# 100_UART_FLASH.net
KiCad netlist of a schematic drawn in Altium Designer
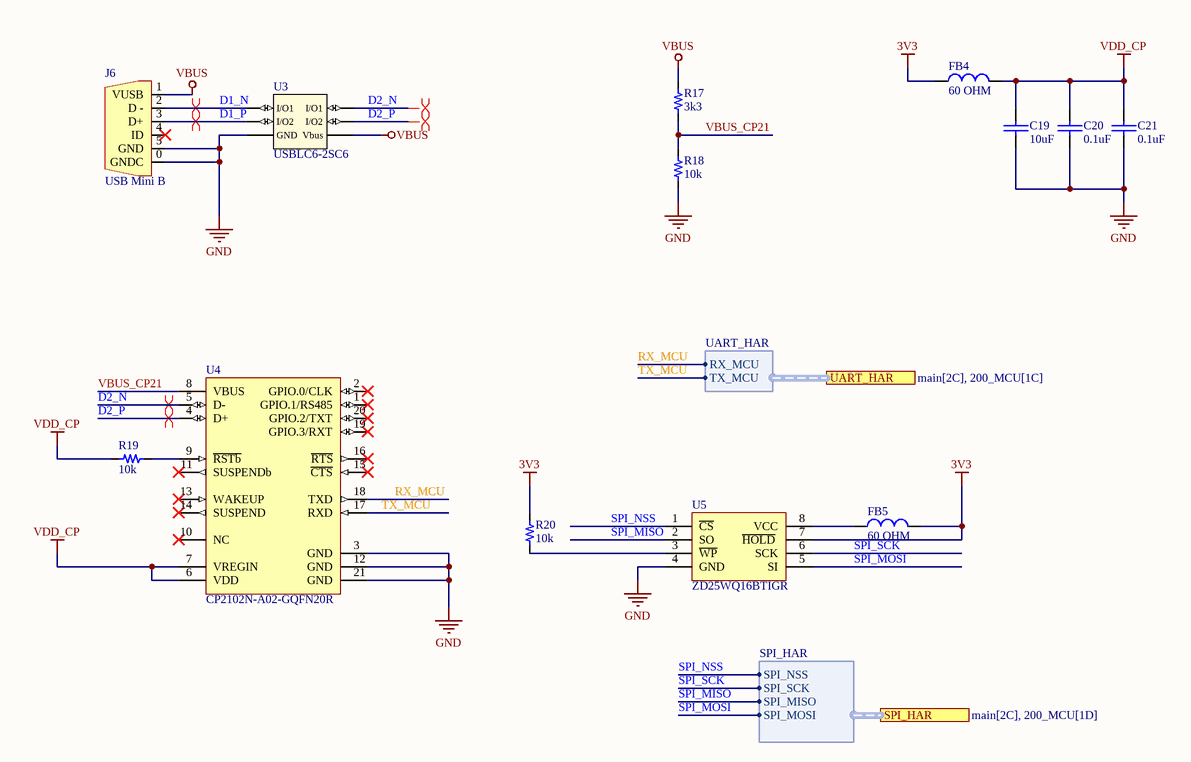
[diagram p0: 100_UART_FLASH.SchDoc]

(export (version "E")
  (design (tool "Eeschema 10.0.6"))
  (components
    (comp (ref "C19")
      (value "10uF")
      (footprint "0603_cap")
      (description "10V 10uF X5R ±10% 0603 Multilayer Ceramic Capacitors MLCC - SMD/SMT ROHS")
      (fields
        (field (name "MANUFACTURER") "CCTC")
        (field (name "MANUFACTURER PART NUMBER") "TCC0603X5R106K100CT")
      )
      (libsource (lib "shared_lib") (part "Cap_10uF_0603_10V"))
    )
    (comp (ref "C20")
      (value "0.1uF")
      (footprint "0603_cap")
      (description "50V 100nF Y5V -20%~+80% 0603 Multilayer Ceramic Capacitors MLCC - SMD/SMT ROHS")
      (fields
        (field (name "MANUFACTURER") "Walsin Tech Corp")
        (field (name "MANUFACTURER PART NUMBER") "0603F104Z500CT")
      )
      (libsource (lib "shared_lib") (part "Cap_0.1uF_0603_50V"))
    )
    (comp (ref "C21")
      (value "0.1uF")
      (footprint "0603_cap")
      (description "50V 100nF Y5V -20%~+80% 0603 Multilayer Ceramic Capacitors MLCC - SMD/SMT ROHS")
      (fields
        (field (name "MANUFACTURER") "Walsin Tech Corp")
        (field (name "MANUFACTURER PART NUMBER") "0603F104Z500CT")
      )
      (libsource (lib "shared_lib") (part "Cap_0.1uF_0603_50V"))
    )
    (comp (ref "FB4")
      (value "60 OHM")
      (footprint "0603_fb")
      (description "2A 1 100mΩ 60Ω@100MHz ±25% 0603 Ferrite Beads ROHS")
      (fields
        (field (name "MANUFACTURER") "TAI-TECH")
        (field (name "MANUFACTURER PART NUMBER") "HCB1608KF-600T20")
      )
      (libsource (lib "shared_lib") (part "FB_60_0603_2A"))
    )
    (comp (ref "FB5")
      (value "60 OHM")
      (footprint "0603_fb")
      (description "2A 1 100mΩ 60Ω@100MHz ±25% 0603 Ferrite Beads ROHS")
      (fields
        (field (name "MANUFACTURER") "TAI-TECH")
        (field (name "MANUFACTURER PART NUMBER") "HCB1608KF-600T20")
      )
      (libsource (lib "shared_lib") (part "FB_60_0603_2A"))
    )
    (comp (ref "J6")
      (value "USB Mini B")
      (footprint "CON_5x1_SMD_miniUSB_B")
      (description "CONN RCPT USB2.0 MINI B SMD R/A")
      (fields
        (field (name "MANUFACTURER PART NUMBER") "KH-MINI-SMT-5P-Cu")
        (field (name "MANUFACTURER") "EDAC Inc.")
      )
      (libsource (lib "shared_lib") (part "Con_Mini_USB_B"))
    )
    (comp (ref "R17")
      (value "3k3")
      (footprint "0603_res")
      (description "RES SMD 3k3 OHM 5% 1/10W 0603")
      (fields
        (field (name "MANUFACTURER") "FOJAN")
        (field (name "MANUFACTURER PART NUMBER") "FRC0603J332 TS")
      )
      (libsource (lib "shared_lib") (part "Res_3k3_0603_1/10W"))
    )
    (comp (ref "R18")
      (value "10k")
      (footprint "0603_res")
      (description "RES SMD 10k OHM 5% 1/10W 0603")
      (fields (field (name "MANUFACTURER") "FOJAN") (field (name "MANUFACTURER PART NUMBER") "FRC0603J103TS"))
      (libsource (lib "shared_lib") (part "Res_10k_0603_1/10W"))
    )
    (comp (ref "R19")
      (value "10k")
      (footprint "0603_res")
      (description "RES SMD 10k OHM 5% 1/10W 0603")
      (fields (field (name "MANUFACTURER") "FOJAN") (field (name "MANUFACTURER PART NUMBER") "FRC0603J103TS"))
      (libsource (lib "shared_lib") (part "Res_10k_0603_1/10W"))
    )
    (comp (ref "R20")
      (value "10k")
      (footprint "0603_res")
      (description "RES SMD 10k OHM 5% 1/10W 0603")
      (fields (field (name "MANUFACTURER") "FOJAN") (field (name "MANUFACTURER PART NUMBER") "FRC0603J103TS"))
      (libsource (lib "shared_lib") (part "Res_10k_0603_1/10W"))
    )
    (comp (ref "U3")
      (value "USBLC6-2SC6")
      (footprint "SOT_23_6")
      (description "TVS DIODE 5.25V 17V SOT23-6")
      (fields (field (name "MANUFACTURER") "STMicroelectronics"))
      (libsource (lib "shared_lib") (part "TVS_5.25V_2CH_SOT_23_6"))
    )
    (comp (ref "U4")
      (value "CP2102N-A02-GQFN20R")
      (footprint "WFQFN_20_EP_3X3MM")
      (description "IC USB TO UART BRIDGE QFN20")
      (fields (field (name "MANUFACTURER") "Silicon Labs"))
      (libsource (lib "shared_lib") (part "IC_SGL_USB2UART-BRIDGE_20QFN"))
    )
    (comp (ref "U5")
      (value "ZD25WQ16BTIGR")
      (footprint "SOIC_8_3.9mm")
      (description "IC FLASH 16M SPI 85MHZ 8SOP")
      (fields (field (name "MANUFACTURER") "Zetta"))
      (libsource (lib "shared_lib") (part "IC_FLASH_ZD25WQ16BTIGR_8SOP"))
    )
  )
  (nets
    (net (code "3") (name "/D1_N") (class "Default")
      (node (ref "J6") (pin "2") (pinfunction "D_-_2") (pintype "passive"))
      (node (ref "U3") (pin "1") (pinfunction "I/O1_1") (pintype "bidirectional"))
    )
    (net (code "4") (name "/D1_P") (class "Default")
      (node (ref "J6") (pin "3") (pinfunction "D+_3") (pintype "passive"))
      (node (ref "U3") (pin "3") (pinfunction "I/O2_3") (pintype "bidirectional"))
    )
    (net (code "5") (name "/D2_N") (class "Default")
      (node (ref "U3") (pin "6") (pinfunction "I/O1_6") (pintype "bidirectional"))
      (node (ref "U4") (pin "5") (pinfunction "D-_5") (pintype "bidirectional"))
    )
    (net (code "6") (name "/D2_P") (class "Default")
      (node (ref "U3") (pin "4") (pinfunction "I/O2_4") (pintype "bidirectional"))
      (node (ref "U4") (pin "4") (pinfunction "D+_4") (pintype "bidirectional"))
    )
    (net (code "7") (name "/RX_MCU") (class "Default")
      (node (ref "U4") (pin "18") (pinfunction "TXD_18") (pintype "output"))
    )
    (net (code "8") (name "/SPI_MISO") (class "Default")
      (node (ref "U5") (pin "2") (pinfunction "SO_2") (pintype "passive"))
    )
    (net (code "9") (name "/SPI_MOSI") (class "Default")
      (node (ref "U5") (pin "5") (pinfunction "SI_5") (pintype "passive"))
    )
    (net (code "10") (name "/SPI_NSS") (class "Default")
      (node (ref "U5") (pin "1") (pinfunction "~{CS}_1") (pintype "passive"))
    )
    (net (code "11") (name "/SPI_SCK") (class "Default")
      (node (ref "U5") (pin "6") (pinfunction "SCK_6") (pintype "passive"))
    )
    (net (code "12") (name "/TX_MCU") (class "Default")
      (node (ref "U4") (pin "17") (pinfunction "RXD_17") (pintype "input"))
    )
    (net (code "13") (name "/VBUS_CP21") (class "Default")
      (node (ref "R17") (pin "1") (pinfunction "1_1") (pintype "passive"))
      (node (ref "R18") (pin "2") (pinfunction "2_2") (pintype "passive"))
      (node (ref "U4") (pin "8") (pinfunction "VBUS_8") (pintype "power_in"))
    )
    (net (code "16") (name "3V3") (class "Default")
      (node (ref "FB4") (pin "1") (pinfunction "1_1") (pintype "passive"))
      (node (ref "FB5") (pin "2") (pinfunction "2_2") (pintype "passive"))
      (node (ref "R20") (pin "1") (pinfunction "1_1") (pintype "passive"))
      (node (ref "U5") (pin "7") (pinfunction "~{HOLD}_7") (pintype "passive"))
    )
    (net (code "17") (name "GND") (class "Default")
      (node (ref "C19") (pin "2") (pinfunction "2_2") (pintype "passive"))
      (node (ref "C20") (pin "2") (pinfunction "2_2") (pintype "passive"))
      (node (ref "C21") (pin "2") (pinfunction "2_2") (pintype "passive"))
      (node (ref "J6") (pin "0") (pinfunction "GNDC_0") (pintype "passive"))
      (node (ref "J6") (pin "5") (pinfunction "GND_5") (pintype "passive"))
      (node (ref "R18") (pin "1") (pinfunction "1_1") (pintype "passive"))
      (node (ref "U3") (pin "2") (pinfunction "GND_2") (pintype "power_in"))
      (node (ref "U4") (pin "12") (pinfunction "GND_12") (pintype "power_in"))
      (node (ref "U4") (pin "21") (pinfunction "GND_21") (pintype "power_in"))
      (node (ref "U4") (pin "3") (pinfunction "GND_3") (pintype "power_in"))
      (node (ref "U5") (pin "4") (pinfunction "GND_4") (pintype "passive"))
    )
    (net (code "18") (name "Net-(U4-~{RSTb})") (class "Default")
      (node (ref "R19") (pin "1") (pinfunction "1_1") (pintype "passive"))
      (node (ref "U4") (pin "9") (pinfunction "~{RSTb}_9") (pintype "input"))
    )
    (net (code "19") (name "Net-(U5-VCC)") (class "Default")
      (node (ref "FB5") (pin "1") (pinfunction "1_1") (pintype "passive"))
      (node (ref "U5") (pin "8") (pinfunction "VCC_8") (pintype "passive"))
    )
    (net (code "20") (name "Net-(U5-~{WP})") (class "Default")
      (node (ref "R20") (pin "2") (pinfunction "2_2") (pintype "passive"))
      (node (ref "U5") (pin "3") (pinfunction "~{WP}_3") (pintype "passive"))
    )
    (net (code "21") (name "VBUS") (class "Default")
      (node (ref "J6") (pin "1") (pinfunction "VUSB_1") (pintype "passive"))
      (node (ref "R17") (pin "2") (pinfunction "2_2") (pintype "passive"))
      (node (ref "U3") (pin "5") (pinfunction "Vbus_5") (pintype "power_in"))
    )
    (net (code "22") (name "VDD_CP") (class "Default")
      (node (ref "C19") (pin "1") (pinfunction "1_1") (pintype "passive"))
      (node (ref "C20") (pin "1") (pinfunction "1_1") (pintype "passive"))
      (node (ref "C21") (pin "1") (pinfunction "1_1") (pintype "passive"))
      (node (ref "FB4") (pin "2") (pinfunction "2_2") (pintype "passive"))
      (node (ref "R19") (pin "2") (pinfunction "2_2") (pintype "passive"))
      (node (ref "U4") (pin "6") (pinfunction "VDD_6") (pintype "power_in"))
      (node (ref "U4") (pin "7") (pinfunction "VREGIN_7") (pintype "power_in"))
    )
    (net (code "23") (name "unconnected-(J6-ID-Pad4)") (class "Default")
      (node (ref "J6") (pin "4") (pinfunction "ID_4") (pintype "passive+no_connect"))
    )
    (net (code "24") (name "unconnected-(U4-GPIO.0{slash}CLK-Pad2)") (class "Default")
      (node (ref "U4") (pin "2") (pinfunction "GPIO.0/CLK_2") (pintype "bidirectional+no_connect"))
    )
    (net (code "25") (name "unconnected-(U4-GPIO.1{slash}RS485-Pad1)") (class "Default")
      (node (ref "U4") (pin "1") (pinfunction "GPIO.1/RS485_1") (pintype "bidirectional+no_connect"))
    )
    (net (code "26") (name "unconnected-(U4-GPIO.2{slash}TXT-Pad20)") (class "Default")
      (node (ref "U4") (pin "20") (pinfunction "GPIO.2/TXT_20") (pintype "bidirectional+no_connect"))
    )
    (net (code "27") (name "unconnected-(U4-GPIO.3{slash}RXT-Pad19)") (class "Default")
      (node (ref "U4") (pin "19") (pinfunction "GPIO.3/RXT_19") (pintype "bidirectional+no_connect"))
    )
    (net (code "28") (name "unconnected-(U4-NC-Pad10)") (class "Default")
      (node (ref "U4") (pin "10") (pinfunction "NC_10") (pintype "passive+no_connect"))
    )
    (net (code "29") (name "unconnected-(U4-SUSPEND-Pad14)") (class "Default")
      (node (ref "U4") (pin "14") (pinfunction "SUSPEND_14") (pintype "output+no_connect"))
    )
    (net (code "30") (name "unconnected-(U4-SUSPENDb-Pad11)") (class "Default")
      (node (ref "U4") (pin "11") (pinfunction "SUSPENDb_11") (pintype "output+no_connect"))
    )
    (net (code "31") (name "unconnected-(U4-WAKEUP-Pad13)") (class "Default")
      (node (ref "U4") (pin "13") (pinfunction "WAKEUP_13") (pintype "input+no_connect"))
    )
    (net (code "32") (name "unconnected-(U4-~{CTS}-Pad15)") (class "Default")
      (node (ref "U4") (pin "15") (pinfunction "~{CTS}_15") (pintype "input+no_connect"))
    )
    (net (code "33") (name "unconnected-(U4-~{RTS}-Pad16)") (class "Default")
      (node (ref "U4") (pin "16") (pinfunction "~{RTS}_16") (pintype "output+no_connect"))
    )
  )
)
